# C128_AV-Adapter.net
KiCad netlist of a schematic drawn in EAGLE
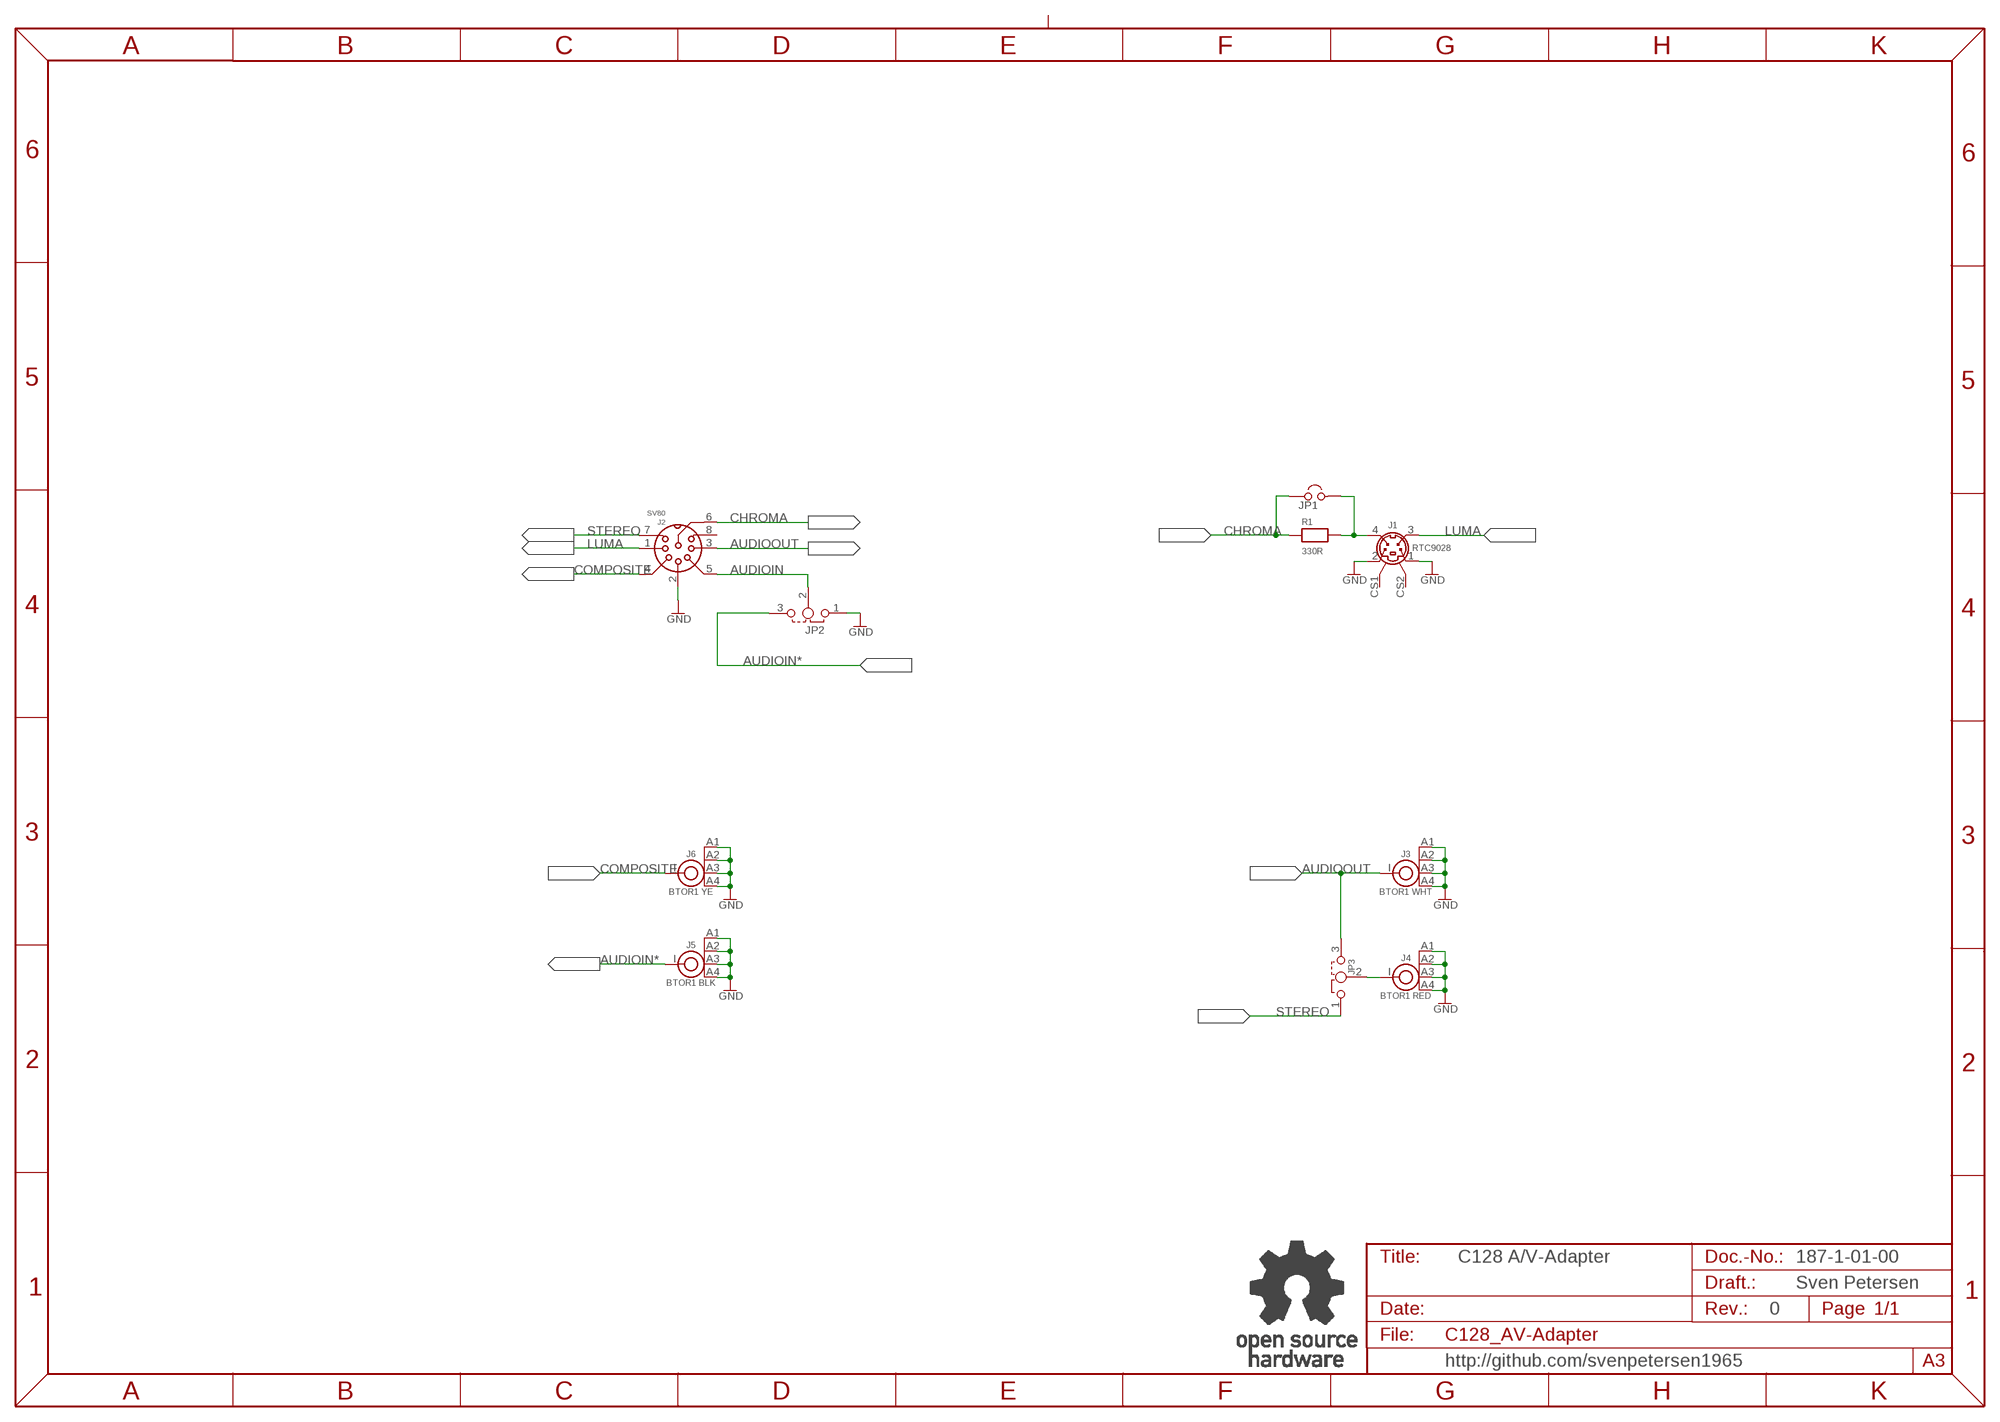
[diagram p0: schematic, sheet 1]

(export (version "E")
  (design (tool "Eeschema 10.0.6"))
  (components
    (comp (ref "J1")
      (value "RTC9028")
      (footprint "eagle-import:MINIDIN4_V")
      (libsource (lib "eagle-import") (part "RTC9028"))
    )
    (comp (ref "J2")
      (value "SV80")
      (footprint "eagle-import:SV80_INNER")
      (libsource (lib "eagle-import") (part "SV80"))
    )
    (comp (ref "J3")
      (value "BTOR1 WHT")
      (footprint "eagle-import:BTOR1")
      (libsource (lib "eagle-import") (part "BTOR1"))
    )
    (comp (ref "J4")
      (value "BTOR1 RED")
      (footprint "eagle-import:BTOR1")
      (libsource (lib "eagle-import") (part "BTOR1"))
    )
    (comp (ref "J5")
      (value "BTOR1 BLK")
      (footprint "eagle-import:BTOR1")
      (libsource (lib "eagle-import") (part "BTOR1"))
    )
    (comp (ref "J6")
      (value "BTOR1 YE")
      (footprint "eagle-import:BTOR1")
      (libsource (lib "eagle-import") (part "BTOR1"))
    )
    (comp (ref "JP1")
      (value "JUMPER")
      (footprint "eagle-import:1X02")
      (libsource (lib "eagle-import") (part "JUMPER"))
    )
    (comp (ref "JP2")
      (value "DJUMPER")
      (footprint "eagle-import:1X03")
      (libsource (lib "eagle-import") (part "DJUMPER"))
    )
    (comp (ref "JP3")
      (value "DJUMPER")
      (footprint "eagle-import:1X03")
      (libsource (lib "eagle-import") (part "DJUMPER"))
    )
    (comp (ref "R1")
      (value "330R")
      (footprint "eagle-import:R-10")
      (libsource (lib "eagle-import") (part "RES04"))
    )
    (comp (ref "U$25")
      (value "OPEN_SOURCE_HW")
      (footprint "eagle-import:OPENHW")
      (libsource (lib "eagle-import") (part "OPEN_SOURCE_HW"))
    )
  )
  (nets
    (net (code "1") (name "/AUDIOIN") (class "Default")
      (node (ref "J2") (pin "5") (pinfunction "5_5") (pintype "bidirectional"))
      (node (ref "JP2") (pin "2") (pinfunction "2_2") (pintype "bidirectional"))
    )
    (net (code "2") (name "/AUDIOIN*") (class "Default")
      (node (ref "J5") (pin "I") (pinfunction "I_I") (pintype "bidirectional"))
      (node (ref "JP2") (pin "3") (pinfunction "3_3") (pintype "bidirectional"))
    )
    (net (code "3") (name "/AUDIOOUT") (class "Default")
      (node (ref "J2") (pin "3") (pinfunction "3_3") (pintype "bidirectional"))
      (node (ref "J3") (pin "I") (pinfunction "I_I") (pintype "bidirectional"))
      (node (ref "JP3") (pin "3") (pinfunction "3_3") (pintype "bidirectional"))
    )
    (net (code "4") (name "/CHROMA") (class "Default")
      (node (ref "J2") (pin "6") (pinfunction "6_6") (pintype "bidirectional"))
      (node (ref "JP1") (pin "1") (pinfunction "1_1") (pintype "bidirectional"))
      (node (ref "R1") (pin "1") (pinfunction "1_1") (pintype "passive"))
    )
    (net (code "5") (name "/COMPOSITE") (class "Default")
      (node (ref "J2") (pin "4") (pinfunction "4_4") (pintype "bidirectional"))
      (node (ref "J6") (pin "I") (pinfunction "I_I") (pintype "bidirectional"))
    )
    (net (code "6") (name "/LUMA") (class "Default")
      (node (ref "J1") (pin "3") (pinfunction "3_3") (pintype "bidirectional"))
      (node (ref "J2") (pin "1") (pinfunction "1_1") (pintype "bidirectional"))
    )
    (net (code "7") (name "/STEREO") (class "Default")
      (node (ref "J2") (pin "7") (pinfunction "7_7") (pintype "bidirectional"))
      (node (ref "JP3") (pin "1") (pinfunction "1_1") (pintype "bidirectional"))
    )
    (net (code "8") (name "GND") (class "Default")
      (node (ref "J1") (pin "1") (pinfunction "1_1") (pintype "bidirectional"))
      (node (ref "J1") (pin "2") (pinfunction "2_2") (pintype "bidirectional"))
      (node (ref "J2") (pin "2") (pinfunction "2_2") (pintype "bidirectional"))
      (node (ref "J3") (pin "A1") (pinfunction "A1_A1") (pintype "bidirectional"))
      (node (ref "J3") (pin "A2") (pinfunction "A2_A2") (pintype "bidirectional"))
      (node (ref "J3") (pin "A3") (pinfunction "A3_A3") (pintype "bidirectional"))
      (node (ref "J3") (pin "A4") (pinfunction "A4_A4") (pintype "bidirectional"))
      (node (ref "J4") (pin "A1") (pinfunction "A1_A1") (pintype "bidirectional"))
      (node (ref "J4") (pin "A2") (pinfunction "A2_A2") (pintype "bidirectional"))
      (node (ref "J4") (pin "A3") (pinfunction "A3_A3") (pintype "bidirectional"))
      (node (ref "J4") (pin "A4") (pinfunction "A4_A4") (pintype "bidirectional"))
      (node (ref "J5") (pin "A1") (pinfunction "A1_A1") (pintype "bidirectional"))
      (node (ref "J5") (pin "A2") (pinfunction "A2_A2") (pintype "bidirectional"))
      (node (ref "J5") (pin "A3") (pinfunction "A3_A3") (pintype "bidirectional"))
      (node (ref "J5") (pin "A4") (pinfunction "A4_A4") (pintype "bidirectional"))
      (node (ref "J6") (pin "A1") (pinfunction "A1_A1") (pintype "bidirectional"))
      (node (ref "J6") (pin "A2") (pinfunction "A2_A2") (pintype "bidirectional"))
      (node (ref "J6") (pin "A3") (pinfunction "A3_A3") (pintype "bidirectional"))
      (node (ref "J6") (pin "A4") (pinfunction "A4_A4") (pintype "bidirectional"))
      (node (ref "JP2") (pin "1") (pinfunction "1_1") (pintype "bidirectional"))
    )
    (net (code "9") (name "Net-(J1-Pad4)") (class "Default")
      (node (ref "J1") (pin "4") (pinfunction "4_4") (pintype "bidirectional"))
      (node (ref "JP1") (pin "2") (pinfunction "2_2") (pintype "bidirectional"))
      (node (ref "R1") (pin "2") (pinfunction "2_2") (pintype "passive"))
    )
    (net (code "10") (name "Net-(J4-PadI)") (class "Default")
      (node (ref "J4") (pin "I") (pinfunction "I_I") (pintype "bidirectional"))
      (node (ref "JP3") (pin "2") (pinfunction "2_2") (pintype "bidirectional"))
    )
    (net (code "11") (name "unconnected-(J1-PadCS1)") (class "Default")
      (node (ref "J1") (pin "CS1") (pinfunction "CS1_CS1") (pintype "bidirectional"))
    )
    (net (code "12") (name "unconnected-(J1-PadCS2)") (class "Default")
      (node (ref "J1") (pin "CS2") (pinfunction "CS2_CS2") (pintype "bidirectional"))
    )
    (net (code "13") (name "unconnected-(J2-Pad8)") (class "Default")
      (node (ref "J2") (pin "8") (pinfunction "8_8") (pintype "bidirectional"))
    )
  )
)
